# uart.net
KiCad netlist of a schematic drawn in Altium Designer
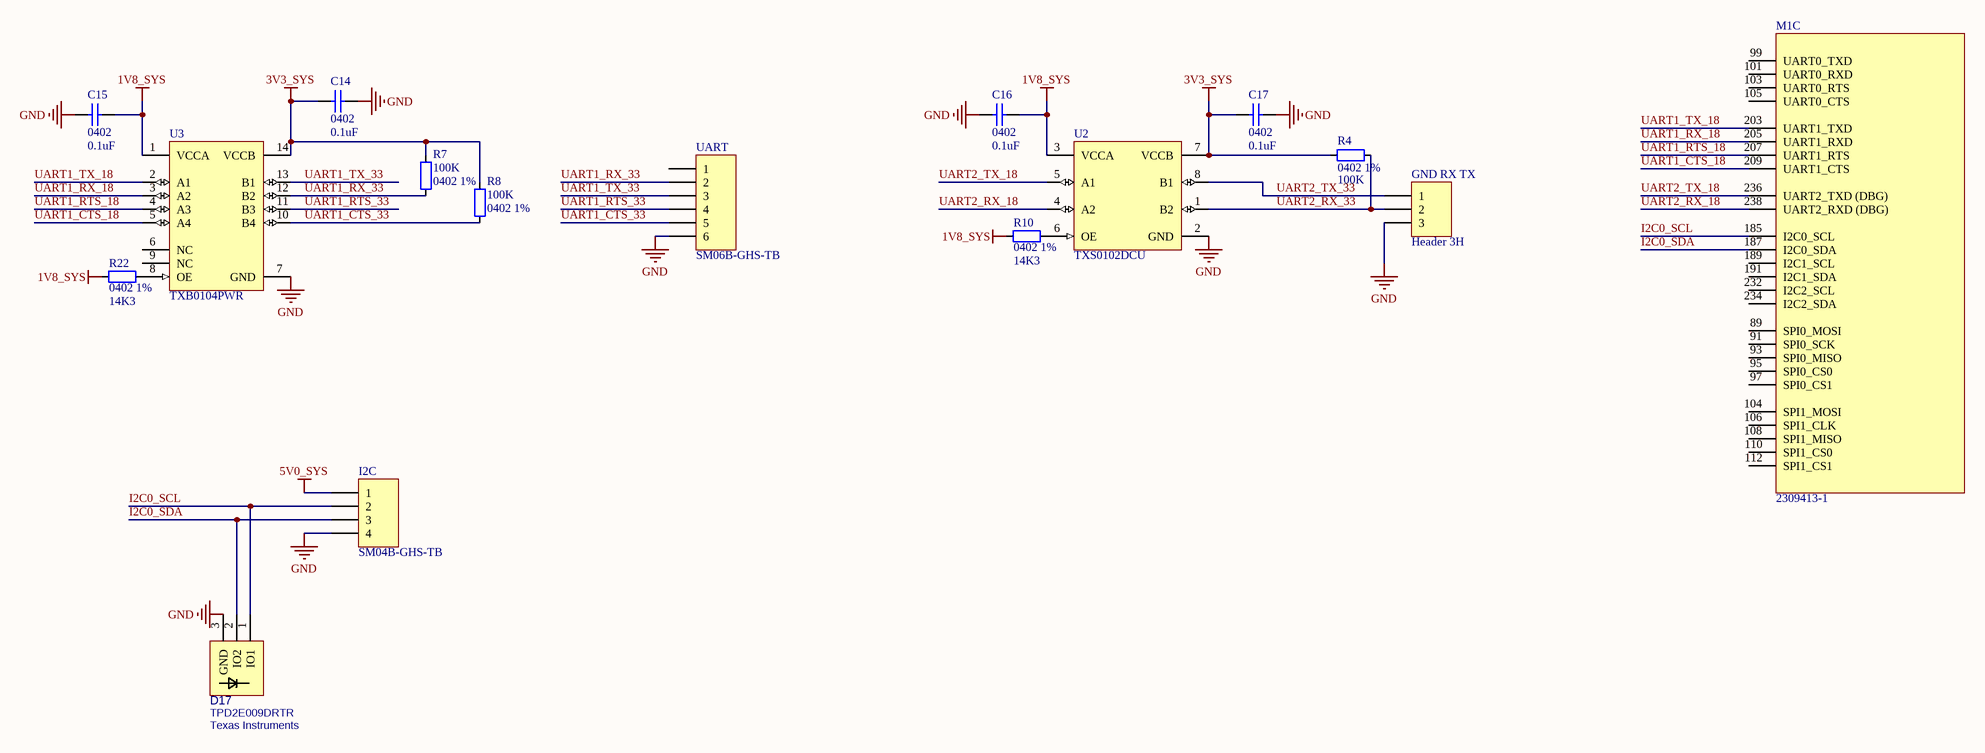
[diagram p0: uart.SchDoc]

(export (version "E")
  (design (tool "Eeschema 10.0.6"))
  (components
    (comp (ref "C14")
      (value "0402")
      (footprint "cap0402")
      (description "standard, non-polarized capacitor")
      (fields (field (name "ALTIUM_VALUE") "0.1uF"))
      (libsource (lib "capacitor") (part "cap"))
    )
    (comp (ref "C15")
      (value "0402")
      (footprint "cap0402")
      (description "standard, non-polarized capacitor")
      (fields (field (name "ALTIUM_VALUE") "0.1uF"))
      (libsource (lib "capacitor") (part "cap"))
    )
    (comp (ref "C16")
      (value "0402")
      (footprint "cap0402")
      (description "standard, non-polarized capacitor")
      (fields (field (name "ALTIUM_VALUE") "0.1uF"))
      (libsource (lib "capacitor") (part "cap"))
    )
    (comp (ref "C17")
      (value "0402")
      (footprint "cap0402")
      (description "standard, non-polarized capacitor")
      (fields (field (name "ALTIUM_VALUE") "0.1uF"))
      (libsource (lib "capacitor") (part "cap"))
    )
    (comp (ref "D17")
      (value "TPD2E009DRTR")
      (footprint "SOT-3")
      (description "ESD Suppressors 2-CH")
      (fields (field (name "MANUFACTURER") "Texas Instruments"))
      (libsource (lib "jetson-nano-baseboard-rev.1.0") (part "TPD2E009"))
    )
    (comp (ref "GND RX TX")
      (value "Header 3H")
      (footprint "header_vert_2.54_3pin")
      (description "Header, 3-Pin, Right Angle")
      (fields (field (name "PUBLISHER") "Altium Limited"))
      (libsource (lib "Miscellaneous Connectors") (part "Header 3H"))
    )
    (comp (ref "I2C")
      (value "SM04B-GHS-TB")
      (footprint "JST_GH_4_side")
      (description "Header, 4-Pin")
      (fields (field (name "PUBLISHER") "Altium Limited"))
      (libsource (lib "Miscellaneous Connectors") (part "Header 4"))
    )
    (comp (ref "M1")
      (value "2309413-1")
      (footprint "jetson-nano-connector")
      (description "Memory Socket, DDR4, SODIMM Socket, 260 Contacts, Copper Alloy, Gold Plated Contacts")
      (fields (field (name "MANUFACTURER") "TE CONNECTIVITY"))
      (libsource (lib "jetson-nano-baseboard") (part "2309413-1"))
    )
    (comp (ref "R4")
      (value "0402 1%")
      (footprint "res0402")
      (description "100K")
      (fields (field (name "ALTIUM_VALUE") "100K"))
      (libsource (lib "resistor") (part "res"))
    )
    (comp (ref "R7")
      (value "0402 1%")
      (footprint "res0402")
      (description "100K")
      (fields (field (name "ALTIUM_VALUE") "100K"))
      (libsource (lib "") (part "res_1"))
    )
    (comp (ref "R8")
      (value "0402 1%")
      (footprint "res0402")
      (description "100K")
      (fields (field (name "ALTIUM_VALUE") "100K"))
      (libsource (lib "") (part "res_1"))
    )
    (comp (ref "R10")
      (value "0402 1%")
      (footprint "res0402")
      (fields (field (name "ALTIUM_VALUE") "14K3"))
      (libsource (lib "resistor") (part "res"))
    )
    (comp (ref "R22")
      (value "0402 1%")
      (footprint "res0402")
      (fields (field (name "ALTIUM_VALUE") "14K3"))
      (libsource (lib "resistor") (part "res"))
    )
    (comp (ref "U2")
      (value "TXS0102DCU")
      (footprint "TSOP8_065pitch")
      (description "Bidirectional voltage level translator")
      (libsource (lib "volt_lvl_translator") (part "TXS0102DCU"))
    )
    (comp (ref "U3")
      (value "TXB0104PWR")
      (footprint "PW0014A_L")
      (description "Bidir. voltage level translator")
      (libsource (lib "volt_lvl_translator") (part "TXB0104PWR"))
    )
    (comp (ref "UART")
      (value "SM06B-GHS-TB")
      (footprint "JST_GH_6_side")
      (description "Header, 6-Pin")
      (fields (field (name "PUBLISHER") "Altium Limited"))
      (libsource (lib "Miscellaneous Connectors") (part "Header 6"))
    )
  )
  (nets
    (net (code "1") (name "/I2C0_SCL") (class "Default")
      (node (ref "D17") (pin "1") (pinfunction "IO1_1") (pintype "passive"))
      (node (ref "I2C") (pin "2") (pinfunction "2_2") (pintype "passive"))
      (node (ref "M1") (pin "185") (pinfunction "I2C0_SCL_185") (pintype "passive"))
    )
    (net (code "2") (name "/I2C0_SDA") (class "Default")
      (node (ref "D17") (pin "2") (pinfunction "IO2_2") (pintype "passive"))
      (node (ref "I2C") (pin "3") (pinfunction "3_3") (pintype "passive"))
      (node (ref "M1") (pin "187") (pinfunction "I2C0_SDA_187") (pintype "passive"))
    )
    (net (code "3") (name "/UART1_CTS_18") (class "Default")
      (node (ref "M1") (pin "209") (pinfunction "UART1_CTS_209") (pintype "passive"))
      (node (ref "U3") (pin "5") (pinfunction "A4_5") (pintype "bidirectional"))
    )
    (net (code "4") (name "/UART1_CTS_33") (class "Default")
      (node (ref "R8") (pin "1") (pinfunction "1_1") (pintype "passive"))
      (node (ref "U3") (pin "10") (pinfunction "B4_10") (pintype "bidirectional"))
      (node (ref "UART") (pin "5") (pinfunction "5_5") (pintype "passive"))
    )
    (net (code "5") (name "/UART1_RTS_18") (class "Default")
      (node (ref "M1") (pin "207") (pinfunction "UART1_RTS_207") (pintype "passive"))
      (node (ref "U3") (pin "4") (pinfunction "A3_4") (pintype "bidirectional"))
    )
    (net (code "6") (name "/UART1_RTS_33") (class "Default")
      (node (ref "U3") (pin "11") (pinfunction "B3_11") (pintype "bidirectional"))
      (node (ref "UART") (pin "4") (pinfunction "4_4") (pintype "passive"))
    )
    (net (code "7") (name "/UART1_RX_18") (class "Default")
      (node (ref "M1") (pin "205") (pinfunction "UART1_RXD_205") (pintype "passive"))
      (node (ref "U3") (pin "3") (pinfunction "A2_3") (pintype "bidirectional"))
    )
    (net (code "8") (name "/UART1_RX_33") (class "Default")
      (node (ref "R7") (pin "1") (pinfunction "1_1") (pintype "passive"))
      (node (ref "U3") (pin "12") (pinfunction "B2_12") (pintype "bidirectional"))
      (node (ref "UART") (pin "2") (pinfunction "2_2") (pintype "passive"))
    )
    (net (code "9") (name "/UART1_TX_18") (class "Default")
      (node (ref "M1") (pin "203") (pinfunction "UART1_TXD_203") (pintype "passive"))
      (node (ref "U3") (pin "2") (pinfunction "A1_2") (pintype "bidirectional"))
    )
    (net (code "10") (name "/UART1_TX_33") (class "Default")
      (node (ref "U3") (pin "13") (pinfunction "B1_13") (pintype "bidirectional"))
      (node (ref "UART") (pin "3") (pinfunction "3_3") (pintype "passive"))
    )
    (net (code "11") (name "/UART2_RX_18") (class "Default")
      (node (ref "M1") (pin "238") (pinfunction "UART2_RXD_(DBG)_238") (pintype "passive"))
      (node (ref "U2") (pin "4") (pinfunction "A2_4") (pintype "bidirectional"))
    )
    (net (code "12") (name "/UART2_RX_33") (class "Default")
      (node (ref "GND RX TX") (pin "2") (pinfunction "2_2") (pintype "passive"))
      (node (ref "R4") (pin "1") (pinfunction "1_1") (pintype "passive"))
      (node (ref "U2") (pin "1") (pinfunction "B2_1") (pintype "bidirectional"))
    )
    (net (code "13") (name "/UART2_TX_18") (class "Default")
      (node (ref "M1") (pin "236") (pinfunction "UART2_TXD_(DBG)_236") (pintype "passive"))
      (node (ref "U2") (pin "5") (pinfunction "A1_5") (pintype "bidirectional"))
    )
    (net (code "14") (name "/UART2_TX_33") (class "Default")
      (node (ref "GND RX TX") (pin "1") (pinfunction "1_1") (pintype "passive"))
      (node (ref "U2") (pin "8") (pinfunction "B1_8") (pintype "bidirectional"))
    )
    (net (code "15") (name "1V8_SYS") (class "Default")
      (node (ref "C15") (pin "1") (pinfunction "1_1") (pintype "passive"))
      (node (ref "C16") (pin "1") (pinfunction "1_1") (pintype "passive"))
      (node (ref "R10") (pin "2") (pinfunction "2_2") (pintype "passive"))
      (node (ref "R22") (pin "2") (pinfunction "2_2") (pintype "passive"))
      (node (ref "U2") (pin "3") (pinfunction "VCCA_3") (pintype "power_in"))
      (node (ref "U3") (pin "1") (pinfunction "VCCA_1") (pintype "power_in"))
    )
    (net (code "16") (name "3V3_SYS") (class "Default")
      (node (ref "C14") (pin "2") (pinfunction "2_2") (pintype "passive"))
      (node (ref "C17") (pin "2") (pinfunction "2_2") (pintype "passive"))
      (node (ref "R4") (pin "2") (pinfunction "2_2") (pintype "passive"))
      (node (ref "R7") (pin "2") (pinfunction "2_2") (pintype "passive"))
      (node (ref "R8") (pin "2") (pinfunction "2_2") (pintype "passive"))
      (node (ref "U2") (pin "7") (pinfunction "VCCB_7") (pintype "power_in"))
      (node (ref "U3") (pin "14") (pinfunction "VCCB_14") (pintype "power_in"))
    )
    (net (code "17") (name "5V0_SYS") (class "Default")
      (node (ref "I2C") (pin "1") (pinfunction "1_1") (pintype "passive"))
    )
    (net (code "18") (name "GND") (class "Default")
      (node (ref "C14") (pin "1") (pinfunction "1_1") (pintype "passive"))
      (node (ref "C15") (pin "2") (pinfunction "2_2") (pintype "passive"))
      (node (ref "C16") (pin "2") (pinfunction "2_2") (pintype "passive"))
      (node (ref "C17") (pin "1") (pinfunction "1_1") (pintype "passive"))
      (node (ref "D17") (pin "3") (pinfunction "GND_3") (pintype "passive"))
      (node (ref "GND RX TX") (pin "3") (pinfunction "3_3") (pintype "passive"))
      (node (ref "I2C") (pin "4") (pinfunction "4_4") (pintype "passive"))
      (node (ref "U2") (pin "2") (pinfunction "GND_2") (pintype "power_in"))
      (node (ref "U3") (pin "7") (pinfunction "GND_7") (pintype "power_in"))
      (node (ref "UART") (pin "6") (pinfunction "6_6") (pintype "passive"))
    )
    (net (code "19") (name "Net-(U2-OE)") (class "Default")
      (node (ref "R10") (pin "1") (pinfunction "1_1") (pintype "passive"))
      (node (ref "U2") (pin "6") (pinfunction "OE_6") (pintype "input"))
    )
    (net (code "20") (name "Net-(U3-OE)") (class "Default")
      (node (ref "R22") (pin "1") (pinfunction "1_1") (pintype "passive"))
      (node (ref "U3") (pin "8") (pinfunction "OE_8") (pintype "input"))
    )
    (net (code "21") (name "unconnected-(M1C-I2C1_SCL-Pad189)") (class "Default")
      (node (ref "M1") (pin "189") (pinfunction "I2C1_SCL_189") (pintype "passive"))
    )
    (net (code "22") (name "unconnected-(M1C-I2C1_SDA-Pad191)") (class "Default")
      (node (ref "M1") (pin "191") (pinfunction "I2C1_SDA_191") (pintype "passive"))
    )
    (net (code "23") (name "unconnected-(M1C-I2C2_SCL-Pad232)") (class "Default")
      (node (ref "M1") (pin "232") (pinfunction "I2C2_SCL_232") (pintype "passive"))
    )
    (net (code "24") (name "unconnected-(M1C-I2C2_SDA-Pad234)") (class "Default")
      (node (ref "M1") (pin "234") (pinfunction "I2C2_SDA_234") (pintype "passive"))
    )
    (net (code "25") (name "unconnected-(M1C-SPI0_CS0-Pad95)") (class "Default")
      (node (ref "M1") (pin "95") (pinfunction "SPI0_CS0_95") (pintype "passive"))
    )
    (net (code "26") (name "unconnected-(M1C-SPI0_CS1-Pad97)") (class "Default")
      (node (ref "M1") (pin "97") (pinfunction "SPI0_CS1_97") (pintype "passive"))
    )
    (net (code "27") (name "unconnected-(M1C-SPI0_MISO-Pad93)") (class "Default")
      (node (ref "M1") (pin "93") (pinfunction "SPI0_MISO_93") (pintype "passive"))
    )
    (net (code "28") (name "unconnected-(M1C-SPI0_MOSI-Pad89)") (class "Default")
      (node (ref "M1") (pin "89") (pinfunction "SPI0_MOSI_89") (pintype "passive"))
    )
    (net (code "29") (name "unconnected-(M1C-SPI0_SCK-Pad91)") (class "Default")
      (node (ref "M1") (pin "91") (pinfunction "SPI0_SCK_91") (pintype "passive"))
    )
    (net (code "30") (name "unconnected-(M1C-SPI1_CLK-Pad106)") (class "Default")
      (node (ref "M1") (pin "106") (pinfunction "SPI1_CLK_106") (pintype "passive"))
    )
    (net (code "31") (name "unconnected-(M1C-SPI1_CS0-Pad110)") (class "Default")
      (node (ref "M1") (pin "110") (pinfunction "SPI1_CS0_110") (pintype "passive"))
    )
    (net (code "32") (name "unconnected-(M1C-SPI1_CS1-Pad112)") (class "Default")
      (node (ref "M1") (pin "112") (pinfunction "SPI1_CS1_112") (pintype "passive"))
    )
    (net (code "33") (name "unconnected-(M1C-SPI1_MISO-Pad108)") (class "Default")
      (node (ref "M1") (pin "108") (pinfunction "SPI1_MISO_108") (pintype "passive"))
    )
    (net (code "34") (name "unconnected-(M1C-SPI1_MOSI-Pad104)") (class "Default")
      (node (ref "M1") (pin "104") (pinfunction "SPI1_MOSI_104") (pintype "passive"))
    )
    (net (code "35") (name "unconnected-(M1C-UART0_CTS-Pad105)") (class "Default")
      (node (ref "M1") (pin "105") (pinfunction "UART0_CTS_105") (pintype "passive"))
    )
    (net (code "36") (name "unconnected-(M1C-UART0_RTS-Pad103)") (class "Default")
      (node (ref "M1") (pin "103") (pinfunction "UART0_RTS_103") (pintype "passive"))
    )
    (net (code "37") (name "unconnected-(M1C-UART0_RXD-Pad101)") (class "Default")
      (node (ref "M1") (pin "101") (pinfunction "UART0_RXD_101") (pintype "passive"))
    )
    (net (code "38") (name "unconnected-(M1C-UART0_TXD-Pad99)") (class "Default")
      (node (ref "M1") (pin "99") (pinfunction "UART0_TXD_99") (pintype "passive"))
    )
    (net (code "39") (name "unconnected-(U3-NC-Pad6)") (class "Default")
      (node (ref "U3") (pin "6") (pinfunction "NC_6") (pintype "passive"))
    )
    (net (code "40") (name "unconnected-(U3-NC-Pad9)") (class "Default")
      (node (ref "U3") (pin "9") (pinfunction "NC_9") (pintype "passive"))
    )
    (net (code "41") (name "unconnected-(UART-Pad1)") (class "Default")
      (node (ref "UART") (pin "1") (pinfunction "1_1") (pintype "passive"))
    )
  )
)
